# Remote_Feedback.net
KiCad netlist of a schematic drawn in Altium Designer
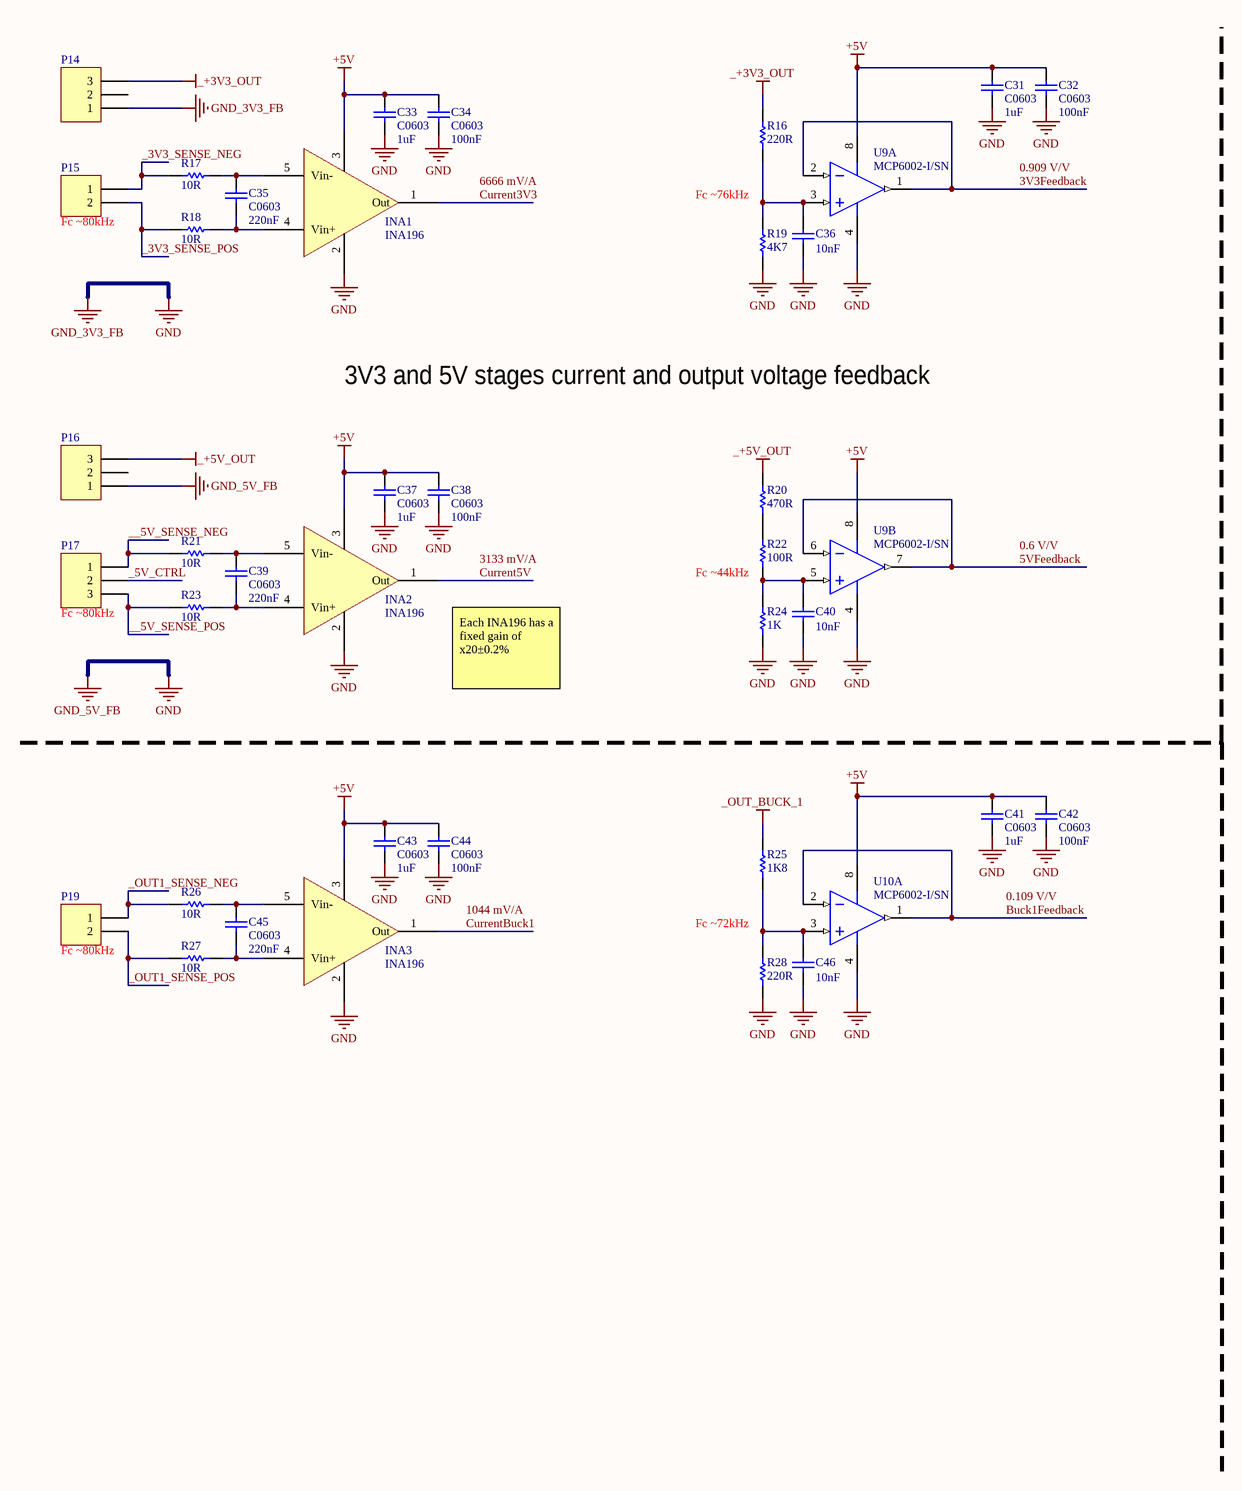
[diagram p0: Remote Feedback.SchDoc]

(export (version "E")
  (design (tool "Eeschema 10.0.6"))
  (components
    (comp (ref "C31")
      (value "C0603")
      (footprint "0603")
      (description "C1608X7R1C105K X7R")
      (fields (field (name "ALTIUM_VALUE") "1uF") (field (name "PUBLISHER") "Altium Limited"))
      (libsource (lib "KEMET Chip Capacitor") (part "C0603"))
    )
    (comp (ref "C32")
      (value "C0603")
      (footprint "0603")
      (description "C1608X7R1C105K X7R")
      (fields (field (name "ALTIUM_VALUE") "100nF") (field (name "PUBLISHER") "Altium Limited"))
      (libsource (lib "KEMET Chip Capacitor") (part "C0603"))
    )
    (comp (ref "C33")
      (value "C0603")
      (footprint "0603")
      (description "C1608X7R1C105K X7R")
      (fields (field (name "ALTIUM_VALUE") "1uF") (field (name "PUBLISHER") "Altium Limited"))
      (libsource (lib "KEMET Chip Capacitor") (part "C0603"))
    )
    (comp (ref "C34")
      (value "C0603")
      (footprint "0603")
      (description "C1608X7R1C105K X7R")
      (fields (field (name "ALTIUM_VALUE") "100nF") (field (name "PUBLISHER") "Altium Limited"))
      (libsource (lib "KEMET Chip Capacitor") (part "C0603"))
    )
    (comp (ref "C35")
      (value "C0603")
      (footprint "0603")
      (description "C1608X7R1C105K X7R")
      (fields (field (name "ALTIUM_VALUE") "220nF") (field (name "PUBLISHER") "Altium Limited"))
      (libsource (lib "KEMET Chip Capacitor") (part "C0603"))
    )
    (comp (ref "C36")
      (value "10nF")
      (footprint "C0805")
      (description "Ceramic Chip Capacitor - MIL-PRF-55681")
      (fields (field (name "Comment") "CDR01") (field (name "PUBLISHER") "Altium Limited"))
      (libsource (lib "KEMET Chip Capacitor") (part "CDR01"))
    )
    (comp (ref "C37")
      (value "C0603")
      (footprint "0603")
      (description "C1608X7R1C105K X7R")
      (fields (field (name "ALTIUM_VALUE") "1uF") (field (name "PUBLISHER") "Altium Limited"))
      (libsource (lib "KEMET Chip Capacitor") (part "C0603"))
    )
    (comp (ref "C38")
      (value "C0603")
      (footprint "0603")
      (description "C1608X7R1C105K X7R")
      (fields (field (name "ALTIUM_VALUE") "100nF") (field (name "PUBLISHER") "Altium Limited"))
      (libsource (lib "KEMET Chip Capacitor") (part "C0603"))
    )
    (comp (ref "C39")
      (value "C0603")
      (footprint "0603")
      (description "C1608X7R1C105K X7R")
      (fields (field (name "ALTIUM_VALUE") "220nF") (field (name "PUBLISHER") "Altium Limited"))
      (libsource (lib "KEMET Chip Capacitor") (part "C0603"))
    )
    (comp (ref "C40")
      (value "10nF")
      (footprint "C0805")
      (description "Ceramic Chip Capacitor - MIL-PRF-55681")
      (fields (field (name "Comment") "CDR01") (field (name "PUBLISHER") "Altium Limited"))
      (libsource (lib "KEMET Chip Capacitor") (part "CDR01"))
    )
    (comp (ref "C41")
      (value "C0603")
      (footprint "0603")
      (description "C1608X7R1C105K X7R")
      (fields (field (name "ALTIUM_VALUE") "1uF") (field (name "PUBLISHER") "Altium Limited"))
      (libsource (lib "KEMET Chip Capacitor") (part "C0603"))
    )
    (comp (ref "C42")
      (value "C0603")
      (footprint "0603")
      (description "C1608X7R1C105K X7R")
      (fields (field (name "ALTIUM_VALUE") "100nF") (field (name "PUBLISHER") "Altium Limited"))
      (libsource (lib "KEMET Chip Capacitor") (part "C0603"))
    )
    (comp (ref "C43")
      (value "C0603")
      (footprint "0603")
      (description "C1608X7R1C105K X7R")
      (fields (field (name "ALTIUM_VALUE") "1uF") (field (name "PUBLISHER") "Altium Limited"))
      (libsource (lib "KEMET Chip Capacitor") (part "C0603"))
    )
    (comp (ref "C44")
      (value "C0603")
      (footprint "0603")
      (description "C1608X7R1C105K X7R")
      (fields (field (name "ALTIUM_VALUE") "100nF") (field (name "PUBLISHER") "Altium Limited"))
      (libsource (lib "KEMET Chip Capacitor") (part "C0603"))
    )
    (comp (ref "C45")
      (value "C0603")
      (footprint "0603")
      (description "C1608X7R1C105K X7R")
      (fields (field (name "ALTIUM_VALUE") "220nF") (field (name "PUBLISHER") "Altium Limited"))
      (libsource (lib "KEMET Chip Capacitor") (part "C0603"))
    )
    (comp (ref "C46")
      (value "10nF")
      (footprint "C0805")
      (description "Ceramic Chip Capacitor - MIL-PRF-55681")
      (fields (field (name "Comment") "CDR01") (field (name "PUBLISHER") "Altium Limited"))
      (libsource (lib "KEMET Chip Capacitor") (part "CDR01"))
    )
    (comp (ref "INA1")
      (value "INA196")
      (footprint "SOT-23-5")
      (description "Current Shunt Monitor −16 V to +80 V Common-Mode Range")
      (libsource (lib "NXT - IC") (part "INA196"))
    )
    (comp (ref "INA2")
      (value "INA196")
      (footprint "SOT-23-5")
      (description "Current Shunt Monitor −16 V to +80 V Common-Mode Range")
      (libsource (lib "NXT - IC") (part "INA196"))
    )
    (comp (ref "INA3")
      (value "INA196")
      (footprint "SOT-23-5")
      (description "Current Shunt Monitor −16 V to +80 V Common-Mode Range")
      (libsource (lib "NXT - IC") (part "INA196"))
    )
    (comp (ref "P14")
      (value "Header 3")
      (footprint "My_1X03")
      (description "Header, 3-Pin")
      (fields (field (name "PUBLISHER") "Altium Limited"))
      (libsource (lib "Mylib") (part "Header 3"))
    )
    (comp (ref "P15")
      (value "Header 2")
      (footprint "My_1X02")
      (description "Header, 2-Pin")
      (fields (field (name "PUBLISHER") "Altium Limited"))
      (libsource (lib "Mylib") (part "Header 2"))
    )
    (comp (ref "P16")
      (value "Header 3")
      (footprint "My_1X03")
      (description "Header, 3-Pin")
      (fields (field (name "PUBLISHER") "Altium Limited"))
      (libsource (lib "Mylib") (part "Header 3"))
    )
    (comp (ref "P17")
      (value "Header 3")
      (footprint "My_1X03")
      (description "Header, 3-Pin")
      (fields (field (name "PUBLISHER") "Altium Limited"))
      (libsource (lib "") (part "Header 3_1"))
    )
    (comp (ref "P19")
      (value "Header 2")
      (footprint "My_1X02")
      (description "Header, 2-Pin")
      (fields (field (name "PUBLISHER") "Altium Limited"))
      (libsource (lib "Mylib") (part "Header 2"))
    )
    (comp (ref "R16")
      (value "220R")
      (footprint "8RB-1206")
      (fields (field (name "Comment") "SMD") (field (name "PUBLISHER") "Altium Limited"))
      (libsource (lib "Panasonic Resistor") (part "ERJ8BQ"))
    )
    (comp (ref "R17")
      (value "10R")
      (footprint "ERA-0603")
      (fields (field (name "PUBLISHER") "Altium Limited"))
      (libsource (lib "Panasonic Resistor") (part "ERA3Y"))
    )
    (comp (ref "R18")
      (value "10R")
      (footprint "ERA-0603")
      (fields (field (name "PUBLISHER") "Altium Limited"))
      (libsource (lib "Panasonic Resistor") (part "ERA3Y"))
    )
    (comp (ref "R19")
      (value "4K7")
      (footprint "8RB-1206")
      (fields (field (name "Comment") "SMD") (field (name "PUBLISHER") "Altium Limited"))
      (libsource (lib "Panasonic Resistor") (part "ERJ8BQ"))
    )
    (comp (ref "R20")
      (value "470R")
      (footprint "8RB-1206")
      (fields (field (name "Comment") "SMD") (field (name "PUBLISHER") "Altium Limited"))
      (libsource (lib "Panasonic Resistor") (part "ERJ8BQ"))
    )
    (comp (ref "R21")
      (value "10R")
      (footprint "ERA-0603")
      (fields (field (name "PUBLISHER") "Altium Limited"))
      (libsource (lib "Panasonic Resistor") (part "ERA3Y"))
    )
    (comp (ref "R22")
      (value "100R")
      (footprint "8RB-1206")
      (fields (field (name "Comment") "SMD") (field (name "PUBLISHER") "Altium Limited"))
      (libsource (lib "Panasonic Resistor") (part "ERJ8BQ"))
    )
    (comp (ref "R23")
      (value "10R")
      (footprint "ERA-0603")
      (fields (field (name "PUBLISHER") "Altium Limited"))
      (libsource (lib "Panasonic Resistor") (part "ERA3Y"))
    )
    (comp (ref "R24")
      (value "1K")
      (footprint "8RB-1206")
      (fields (field (name "Comment") "SMD") (field (name "PUBLISHER") "Altium Limited"))
      (libsource (lib "Panasonic Resistor") (part "ERJ8BQ"))
    )
    (comp (ref "R25")
      (value "1K8")
      (footprint "8RB-1206")
      (fields (field (name "Comment") "SMD") (field (name "PUBLISHER") "Altium Limited"))
      (libsource (lib "Panasonic Resistor") (part "ERJ8BQ"))
    )
    (comp (ref "R26")
      (value "10R")
      (footprint "ERA-0603")
      (fields (field (name "PUBLISHER") "Altium Limited"))
      (libsource (lib "Panasonic Resistor") (part "ERA3Y"))
    )
    (comp (ref "R27")
      (value "10R")
      (footprint "ERA-0603")
      (fields (field (name "PUBLISHER") "Altium Limited"))
      (libsource (lib "Panasonic Resistor") (part "ERA3Y"))
    )
    (comp (ref "R28")
      (value "220R")
      (footprint "8RB-1206")
      (fields (field (name "Comment") "SMD") (field (name "PUBLISHER") "Altium Limited"))
      (libsource (lib "Panasonic Resistor") (part "ERJ8BQ"))
    )
    (comp (ref "U9")
      (value "MCP6002-I/SN")
      (footprint "SOIC-SN8_N")
      (description "1 MHz, Low-Power Operational Amplifier, 8-Pin SOIC, Industrial Temperature")
      (fields (field (name "MANUFACTURER") "Microchip"))
      (libsource (lib "Microchip Linear") (part "MCP6002-I/SN"))
    )
    (comp (ref "U10")
      (value "MCP6002-I/SN")
      (footprint "SOIC-SN8_N")
      (description "1 MHz, Low-Power Operational Amplifier, 8-Pin SOIC, Industrial Temperature")
      (fields (field (name "MANUFACTURER") "Microchip"))
      (libsource (lib "Microchip Linear") (part "MCP6002-I/SN"))
    )
  )
  (nets
    (net (code "1") (name "+5V") (class "Default")
      (node (ref "C31") (pin "2") (pinfunction "2_2") (pintype "passive"))
      (node (ref "C32") (pin "2") (pinfunction "2_2") (pintype "passive"))
      (node (ref "C33") (pin "2") (pinfunction "2_2") (pintype "passive"))
      (node (ref "C34") (pin "2") (pinfunction "2_2") (pintype "passive"))
      (node (ref "C37") (pin "2") (pinfunction "2_2") (pintype "passive"))
      (node (ref "C38") (pin "2") (pinfunction "2_2") (pintype "passive"))
      (node (ref "C41") (pin "2") (pinfunction "2_2") (pintype "passive"))
      (node (ref "C42") (pin "2") (pinfunction "2_2") (pintype "passive"))
      (node (ref "C43") (pin "2") (pinfunction "2_2") (pintype "passive"))
      (node (ref "C44") (pin "2") (pinfunction "2_2") (pintype "passive"))
      (node (ref "INA1") (pin "3") (pinfunction "3_3") (pintype "passive"))
      (node (ref "INA2") (pin "3") (pinfunction "3_3") (pintype "passive"))
      (node (ref "INA3") (pin "3") (pinfunction "3_3") (pintype "passive"))
      (node (ref "U10") (pin "8") (pinfunction "VDD_8") (pintype "power_in"))
      (node (ref "U9") (pin "8") (pinfunction "VDD_8") (pintype "power_in"))
    )
    (net (code "5") (name "/3V3Feedback") (class "Default")
      (node (ref "U9") (pin "1") (pinfunction "VOUTA_1") (pintype "output"))
      (node (ref "U9") (pin "2") (pinfunction "VINA-_2") (pintype "input"))
    )
    (net (code "6") (name "/5VFeedback") (class "Default")
      (node (ref "U9") (pin "6") (pinfunction "VINB-_6") (pintype "input"))
      (node (ref "U9") (pin "7") (pinfunction "VOUTB_7") (pintype "output"))
    )
    (net (code "10") (name "/Buck1Feedback") (class "Default")
      (node (ref "U10") (pin "1") (pinfunction "VOUTA_1") (pintype "output"))
      (node (ref "U10") (pin "2") (pinfunction "VINA-_2") (pintype "input"))
    )
    (net (code "11") (name "/Current3V3") (class "Default")
      (node (ref "INA1") (pin "1") (pinfunction "Out_1") (pintype "passive"))
    )
    (net (code "12") (name "/Current5V") (class "Default")
      (node (ref "INA2") (pin "1") (pinfunction "Out_1") (pintype "passive"))
    )
    (net (code "13") (name "/CurrentBuck1") (class "Default")
      (node (ref "INA3") (pin "1") (pinfunction "Out_1") (pintype "passive"))
    )
    (net (code "14") (name "/_3V3_SENSE_NEG") (class "Default")
      (node (ref "P15") (pin "1") (pinfunction "1_1") (pintype "passive"))
      (node (ref "R17") (pin "2") (pinfunction "2_2") (pintype "passive"))
    )
    (net (code "15") (name "/_3V3_SENSE_POS") (class "Default")
      (node (ref "P15") (pin "2") (pinfunction "2_2") (pintype "passive"))
      (node (ref "R18") (pin "2") (pinfunction "2_2") (pintype "passive"))
    )
    (net (code "16") (name "/_5V_CTRL") (class "Default")
      (node (ref "P17") (pin "2") (pinfunction "2_2") (pintype "passive"))
    )
    (net (code "17") (name "/_OUT1_SENSE_NEG") (class "Default")
      (node (ref "P19") (pin "1") (pinfunction "1_1") (pintype "passive"))
      (node (ref "R26") (pin "2") (pinfunction "2_2") (pintype "passive"))
    )
    (net (code "18") (name "/_OUT1_SENSE_POS") (class "Default")
      (node (ref "P19") (pin "2") (pinfunction "2_2") (pintype "passive"))
      (node (ref "R27") (pin "2") (pinfunction "2_2") (pintype "passive"))
    )
    (net (code "19") (name "/__5V_SENSE_NEG") (class "Default")
      (node (ref "P17") (pin "1") (pinfunction "1_1") (pintype "passive"))
      (node (ref "R21") (pin "2") (pinfunction "2_2") (pintype "passive"))
    )
    (net (code "20") (name "/__5V_SENSE_POS") (class "Default")
      (node (ref "P17") (pin "3") (pinfunction "3_3") (pintype "passive"))
      (node (ref "R23") (pin "2") (pinfunction "2_2") (pintype "passive"))
    )
    (net (code "21") (name "GND") (class "Default")
      (node (ref "C31") (pin "1") (pinfunction "1_1") (pintype "passive"))
      (node (ref "C32") (pin "1") (pinfunction "1_1") (pintype "passive"))
      (node (ref "C33") (pin "1") (pinfunction "1_1") (pintype "passive"))
      (node (ref "C34") (pin "1") (pinfunction "1_1") (pintype "passive"))
      (node (ref "C36") (pin "1") (pinfunction "1_1") (pintype "passive"))
      (node (ref "C37") (pin "1") (pinfunction "1_1") (pintype "passive"))
      (node (ref "C38") (pin "1") (pinfunction "1_1") (pintype "passive"))
      (node (ref "C40") (pin "1") (pinfunction "1_1") (pintype "passive"))
      (node (ref "C41") (pin "1") (pinfunction "1_1") (pintype "passive"))
      (node (ref "C42") (pin "1") (pinfunction "1_1") (pintype "passive"))
      (node (ref "C43") (pin "1") (pinfunction "1_1") (pintype "passive"))
      (node (ref "C44") (pin "1") (pinfunction "1_1") (pintype "passive"))
      (node (ref "C46") (pin "1") (pinfunction "1_1") (pintype "passive"))
      (node (ref "INA1") (pin "2") (pinfunction "GND_2") (pintype "passive"))
      (node (ref "INA2") (pin "2") (pinfunction "GND_2") (pintype "passive"))
      (node (ref "INA3") (pin "2") (pinfunction "GND_2") (pintype "passive"))
      (node (ref "P14") (pin "1") (pinfunction "1_1") (pintype "passive"))
      (node (ref "P16") (pin "1") (pinfunction "1_1") (pintype "passive"))
      (node (ref "R19") (pin "1") (pinfunction "1_1") (pintype "passive"))
      (node (ref "R24") (pin "1") (pinfunction "1_1") (pintype "passive"))
      (node (ref "R28") (pin "1") (pinfunction "1_1") (pintype "passive"))
      (node (ref "U10") (pin "4") (pinfunction "VSS_4") (pintype "power_in"))
      (node (ref "U9") (pin "4") (pinfunction "VSS_4") (pintype "power_in"))
    )
    (net (code "22") (name "Net-(INA1-Vin+)") (class "Default")
      (node (ref "C35") (pin "1") (pinfunction "1_1") (pintype "passive"))
      (node (ref "INA1") (pin "4") (pinfunction "Vin+_4") (pintype "passive"))
      (node (ref "R18") (pin "1") (pinfunction "1_1") (pintype "passive"))
    )
    (net (code "23") (name "Net-(INA1-Vin-)") (class "Default")
      (node (ref "C35") (pin "2") (pinfunction "2_2") (pintype "passive"))
      (node (ref "INA1") (pin "5") (pinfunction "Vin-_5") (pintype "passive"))
      (node (ref "R17") (pin "1") (pinfunction "1_1") (pintype "passive"))
    )
    (net (code "24") (name "Net-(INA2-Vin+)") (class "Default")
      (node (ref "C39") (pin "1") (pinfunction "1_1") (pintype "passive"))
      (node (ref "INA2") (pin "4") (pinfunction "Vin+_4") (pintype "passive"))
      (node (ref "R23") (pin "1") (pinfunction "1_1") (pintype "passive"))
    )
    (net (code "25") (name "Net-(INA2-Vin-)") (class "Default")
      (node (ref "C39") (pin "2") (pinfunction "2_2") (pintype "passive"))
      (node (ref "INA2") (pin "5") (pinfunction "Vin-_5") (pintype "passive"))
      (node (ref "R21") (pin "1") (pinfunction "1_1") (pintype "passive"))
    )
    (net (code "26") (name "Net-(INA3-Vin+)") (class "Default")
      (node (ref "C45") (pin "1") (pinfunction "1_1") (pintype "passive"))
      (node (ref "INA3") (pin "4") (pinfunction "Vin+_4") (pintype "passive"))
      (node (ref "R27") (pin "1") (pinfunction "1_1") (pintype "passive"))
    )
    (net (code "27") (name "Net-(INA3-Vin-)") (class "Default")
      (node (ref "C45") (pin "2") (pinfunction "2_2") (pintype "passive"))
      (node (ref "INA3") (pin "5") (pinfunction "Vin-_5") (pintype "passive"))
      (node (ref "R26") (pin "1") (pinfunction "1_1") (pintype "passive"))
    )
    (net (code "28") (name "Net-(R20-Pad1)") (class "Default")
      (node (ref "R20") (pin "1") (pinfunction "1_1") (pintype "passive"))
      (node (ref "R22") (pin "2") (pinfunction "2_2") (pintype "passive"))
    )
    (net (code "29") (name "Net-(U9A-VINA+)") (class "Default")
      (node (ref "C36") (pin "2") (pinfunction "2_2") (pintype "passive"))
      (node (ref "R16") (pin "1") (pinfunction "1_1") (pintype "passive"))
      (node (ref "R19") (pin "2") (pinfunction "2_2") (pintype "passive"))
      (node (ref "U9") (pin "3") (pinfunction "VINA+_3") (pintype "input"))
    )
    (net (code "30") (name "Net-(U9B-VINB+)") (class "Default")
      (node (ref "C40") (pin "2") (pinfunction "2_2") (pintype "passive"))
      (node (ref "R22") (pin "1") (pinfunction "1_1") (pintype "passive"))
      (node (ref "R24") (pin "2") (pinfunction "2_2") (pintype "passive"))
      (node (ref "U9") (pin "5") (pinfunction "VINB+_5") (pintype "input"))
    )
    (net (code "31") (name "Net-(U10A-VINA+)") (class "Default")
      (node (ref "C46") (pin "2") (pinfunction "2_2") (pintype "passive"))
      (node (ref "R25") (pin "1") (pinfunction "1_1") (pintype "passive"))
      (node (ref "R28") (pin "2") (pinfunction "2_2") (pintype "passive"))
      (node (ref "U10") (pin "3") (pinfunction "VINA+_3") (pintype "input"))
    )
    (net (code "32") (name "_+3V3_OUT") (class "Default")
      (node (ref "P14") (pin "3") (pinfunction "3_3") (pintype "passive"))
      (node (ref "R16") (pin "2") (pinfunction "2_2") (pintype "passive"))
    )
    (net (code "33") (name "_+5V_OUT") (class "Default")
      (node (ref "P16") (pin "3") (pinfunction "3_3") (pintype "passive"))
      (node (ref "R20") (pin "2") (pinfunction "2_2") (pintype "passive"))
    )
    (net (code "34") (name "_OUT_BUCK_1") (class "Default")
      (node (ref "R25") (pin "2") (pinfunction "2_2") (pintype "passive"))
    )
    (net (code "35") (name "unconnected-(P14-Pad2)") (class "Default")
      (node (ref "P14") (pin "2") (pinfunction "2_2") (pintype "passive"))
    )
    (net (code "36") (name "unconnected-(P16-Pad2)") (class "Default")
      (node (ref "P16") (pin "2") (pinfunction "2_2") (pintype "passive"))
    )
  )
)
